# MCU.net
KiCad netlist of a schematic drawn in Altium Designer
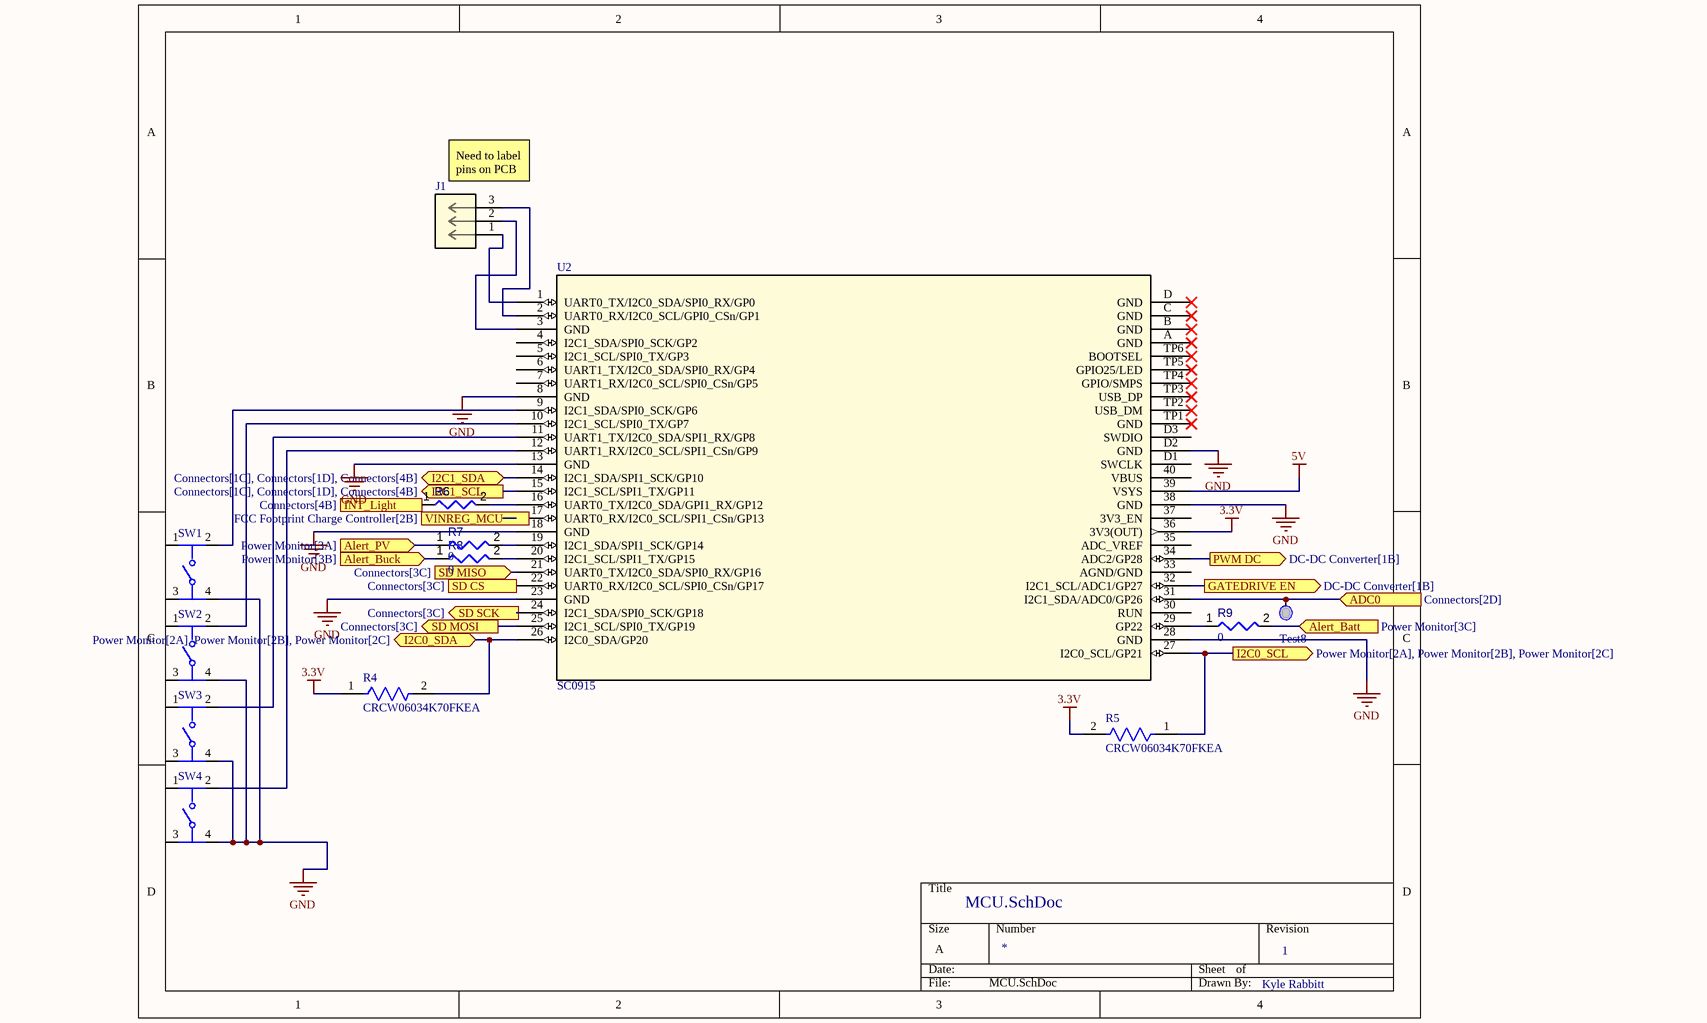
[diagram p0: MCU.SchDoc]

(export (version "E")
  (design (tool "Eeschema 10.0.6"))
  (components
    (comp (ref "J1")
      (value "~")
      (footprint "CONN_BM03B-SRSS-TBLFSN_JST")
      (description "No Description Available")
      (libsource (lib "BM03B-SRSS-TBLFSN") (part "BM03B-SRSS-TBLFSN"))
    )
    (comp (ref "R4")
      (value "CRCW06034K70FKEA")
      (footprint "FP-CRCW0603-e3-IPC_A")
      (description "RES Thick Film, 4.7kΩ, 1%, 0.1W, 100ppm/°C, 0603")
      (fields (field (name "TOLERANCE") "1%"))
      (libsource (lib "Altium Content Vault") (part "1029c3af85768c4190bb7ad29bc67b5"))
    )
    (comp (ref "R5")
      (value "CRCW06034K70FKEA")
      (footprint "FP-CRCW0603-e3-IPC_A")
      (description "RES Thick Film, 4.7kΩ, 1%, 0.1W, 100ppm/°C, 0603")
      (fields (field (name "TOLERANCE") "1%"))
      (libsource (lib "Altium Content Vault") (part "1029c3af85768c4190bb7ad29bc67b5"))
    )
    (comp (ref "R6")
      (value "0")
      (footprint "RESC0603(1608)_L")
      (description "Jumper 0603 (1608 Metric)")
      (fields (field (name "Comment") "0R3J"))
      (libsource (lib "WPI High Power Rocketry Club") (part "0R3J"))
    )
    (comp (ref "R7")
      (value "0")
      (footprint "RESC0603(1608)_L")
      (description "Jumper 0603 (1608 Metric)")
      (fields (field (name "Comment") "0R3J"))
      (libsource (lib "WPI High Power Rocketry Club") (part "0R3J"))
    )
    (comp (ref "R8")
      (value "0")
      (footprint "RESC0603(1608)_L")
      (description "Jumper 0603 (1608 Metric)")
      (fields (field (name "Comment") "0R3J"))
      (libsource (lib "WPI High Power Rocketry Club") (part "0R3J"))
    )
    (comp (ref "R9")
      (value "0")
      (footprint "RESC0603(1608)_L")
      (description "Jumper 0603 (1608 Metric)")
      (fields (field (name "Comment") "0R3J"))
      (libsource (lib "WPI High Power Rocketry Club") (part "0R3J"))
    )
    (comp (ref "SW1")
      (value "~")
      (footprint "FP-PTS645SM43SMTR92LFS-MFG")
      (description "SWITCH TACTILE SPST-NO 0.05A 12V")
      (libsource (lib "Altium Content Vault") (part "1adf0dd01260c80cf25a44bfd6b99ba"))
    )
    (comp (ref "SW2")
      (value "~")
      (footprint "FP-PTS645SM43SMTR92LFS-MFG")
      (description "SWITCH TACTILE SPST-NO 0.05A 12V")
      (libsource (lib "Altium Content Vault") (part "1adf0dd01260c80cf25a44bfd6b99ba"))
    )
    (comp (ref "SW3")
      (value "~")
      (footprint "FP-PTS645SM43SMTR92LFS-MFG")
      (description "SWITCH TACTILE SPST-NO 0.05A 12V")
      (libsource (lib "Altium Content Vault") (part "1adf0dd01260c80cf25a44bfd6b99ba"))
    )
    (comp (ref "SW4")
      (value "~")
      (footprint "FP-PTS645SM43SMTR92LFS-MFG")
      (description "SWITCH TACTILE SPST-NO 0.05A 12V")
      (libsource (lib "Altium Content Vault") (part "1adf0dd01260c80cf25a44bfd6b99ba"))
    )
    (comp (ref "Test8")
      (value "TestPoint")
      (footprint "Test_IN")
      (libsource (lib "Test_POINTS") (part "TestPoint"))
    )
    (comp (ref "U2")
      (value "SC0915")
      (footprint "SC0915_RPI")
      (description "No Description Available")
      (libsource (lib "SC0915") (part "SC0915"))
    )
  )
  (nets
    (net (code "1") (name "/ADC0") (class "Default")
      (node (ref "Test8") (pin "IN") (pinfunction "IN_IN") (pintype "input"))
      (node (ref "U2") (pin "31") (pinfunction "I2C1_SDA/ADC0/GP26_31") (pintype "bidirectional"))
    )
    (net (code "2") (name "/Alert_Batt") (class "Default")
      (node (ref "R9") (pin "2") (pinfunction "2_2") (pintype "passive"))
    )
    (net (code "3") (name "/Alert_Buck") (class "Default")
      (node (ref "R8") (pin "1") (pinfunction "1_1") (pintype "passive"))
    )
    (net (code "4") (name "/Alert_PV") (class "Default")
      (node (ref "R7") (pin "1") (pinfunction "1_1") (pintype "passive"))
    )
    (net (code "5") (name "/GATEDRIVE EN") (class "Default")
      (node (ref "U2") (pin "32") (pinfunction "I2C1_SCL/ADC1/GP27_32") (pintype "bidirectional"))
    )
    (net (code "6") (name "/I2C0_SCL") (class "Default")
      (node (ref "R5") (pin "1") (pinfunction "1_1") (pintype "passive"))
      (node (ref "U2") (pin "27") (pinfunction "I2C0_SCL/GP21_27") (pintype "bidirectional"))
    )
    (net (code "7") (name "/I2C0_SDA") (class "Default")
      (node (ref "R4") (pin "2") (pinfunction "2_2") (pintype "passive"))
      (node (ref "U2") (pin "26") (pinfunction "I2C0_SDA/GP20_26") (pintype "bidirectional"))
    )
    (net (code "8") (name "/I2C1_SCL") (class "Default")
      (node (ref "U2") (pin "15") (pinfunction "I2C1_SCL/SPI1_TX/GP11_15") (pintype "bidirectional"))
    )
    (net (code "9") (name "/I2C1_SDA") (class "Default")
      (node (ref "U2") (pin "14") (pinfunction "I2C1_SDA/SPI1_SCK/GP10_14") (pintype "bidirectional"))
    )
    (net (code "10") (name "/INT_Light") (class "Default")
      (node (ref "R6") (pin "1") (pinfunction "1_1") (pintype "passive"))
    )
    (net (code "11") (name "/PWM DC") (class "Default")
      (node (ref "U2") (pin "34") (pinfunction "ADC2/GP28_34") (pintype "bidirectional"))
    )
    (net (code "12") (name "/SD CS") (class "Default")
      (node (ref "U2") (pin "22") (pinfunction "UART0_RX/I2C0_SCL/SPI0_CSn/GP17_22") (pintype "bidirectional"))
    )
    (net (code "13") (name "/SD MISO") (class "Default")
      (node (ref "U2") (pin "21") (pinfunction "UART0_TX/I2C0_SDA/SPI0_RX/GP16_21") (pintype "bidirectional"))
    )
    (net (code "14") (name "/SD MOSI") (class "Default")
      (node (ref "U2") (pin "25") (pinfunction "I2C1_SCL/SPI0_TX/GP19_25") (pintype "bidirectional"))
    )
    (net (code "15") (name "/SD SCK") (class "Default")
      (node (ref "U2") (pin "24") (pinfunction "I2C1_SDA/SPI0_SCK/GP18_24") (pintype "bidirectional"))
    )
    (net (code "17") (name "3.3V") (class "Default")
      (node (ref "R4") (pin "1") (pinfunction "1_1") (pintype "passive"))
      (node (ref "R5") (pin "2") (pinfunction "2_2") (pintype "passive"))
      (node (ref "U2") (pin "36") (pinfunction "3V3(OUT)_36") (pintype "output"))
    )
    (net (code "18") (name "5V") (class "Default")
      (node (ref "U2") (pin "39") (pinfunction "VSYS_39") (pintype "power_in"))
    )
    (net (code "19") (name "GND") (class "Default")
      (node (ref "SW1") (pin "4") (pinfunction "4_4") (pintype "passive"))
      (node (ref "SW2") (pin "4") (pinfunction "4_4") (pintype "passive"))
      (node (ref "SW3") (pin "4") (pinfunction "4_4") (pintype "passive"))
      (node (ref "SW4") (pin "4") (pinfunction "4_4") (pintype "passive"))
      (node (ref "U2") (pin "13") (pinfunction "GND_13") (pintype "power_in"))
      (node (ref "U2") (pin "18") (pinfunction "GND_18") (pintype "power_in"))
      (node (ref "U2") (pin "23") (pinfunction "GND_23") (pintype "power_in"))
      (node (ref "U2") (pin "28") (pinfunction "GND_28") (pintype "power_in"))
      (node (ref "U2") (pin "38") (pinfunction "GND_38") (pintype "power_in"))
      (node (ref "U2") (pin "8") (pinfunction "GND_8") (pintype "power_in"))
      (node (ref "U2") (pin "D2") (pinfunction "GND_D2") (pintype "power_in"))
    )
    (net (code "20") (name "Net-(J1-Pad2)") (class "Default")
      (node (ref "J1") (pin "2") (pinfunction "2_2") (pintype "passive"))
      (node (ref "U2") (pin "3") (pinfunction "GND_3") (pintype "power_in"))
    )
    (net (code "21") (name "Net-(U2-GP22)") (class "Default")
      (node (ref "R9") (pin "1") (pinfunction "1_1") (pintype "passive"))
      (node (ref "U2") (pin "29") (pinfunction "GP22_29") (pintype "bidirectional"))
    )
    (net (code "22") (name "Net-(U2-I2C1_SCL{slash}SPI0_TX{slash}GP7)") (class "Default")
      (node (ref "SW2") (pin "2") (pinfunction "2_2") (pintype "passive"))
      (node (ref "U2") (pin "10") (pinfunction "I2C1_SCL/SPI0_TX/GP7_10") (pintype "bidirectional"))
    )
    (net (code "23") (name "Net-(U2-I2C1_SCL{slash}SPI1_TX{slash}GP15)") (class "Default")
      (node (ref "R8") (pin "2") (pinfunction "2_2") (pintype "passive"))
      (node (ref "U2") (pin "20") (pinfunction "I2C1_SCL/SPI1_TX/GP15_20") (pintype "bidirectional"))
    )
    (net (code "24") (name "Net-(U2-I2C1_SDA{slash}SPI0_SCK{slash}GP6)") (class "Default")
      (node (ref "SW1") (pin "2") (pinfunction "2_2") (pintype "passive"))
      (node (ref "U2") (pin "9") (pinfunction "I2C1_SDA/SPI0_SCK/GP6_9") (pintype "bidirectional"))
    )
    (net (code "25") (name "Net-(U2-I2C1_SDA{slash}SPI1_SCK{slash}GP14)") (class "Default")
      (node (ref "R7") (pin "2") (pinfunction "2_2") (pintype "passive"))
      (node (ref "U2") (pin "19") (pinfunction "I2C1_SDA/SPI1_SCK/GP14_19") (pintype "bidirectional"))
    )
    (net (code "26") (name "Net-(U2-UART0_RX{slash}I2C0_SCL{slash}GPI0_CSn{slash}GP1)") (class "Default")
      (node (ref "J1") (pin "3") (pinfunction "3_3") (pintype "passive"))
      (node (ref "U2") (pin "2") (pinfunction "UART0_RX/I2C0_SCL/GPI0_CSn/GP1_2") (pintype "bidirectional"))
    )
    (net (code "27") (name "Net-(U2-UART0_TX{slash}I2C0_SDA{slash}GPI1_RX{slash}GP12)") (class "Default")
      (node (ref "R6") (pin "2") (pinfunction "2_2") (pintype "passive"))
      (node (ref "U2") (pin "16") (pinfunction "UART0_TX/I2C0_SDA/GPI1_RX/GP12_16") (pintype "bidirectional"))
    )
    (net (code "28") (name "Net-(U2-UART0_TX{slash}I2C0_SDA{slash}SPI0_RX{slash}GP0)") (class "Default")
      (node (ref "J1") (pin "1") (pinfunction "1_1") (pintype "passive"))
      (node (ref "U2") (pin "1") (pinfunction "UART0_TX/I2C0_SDA/SPI0_RX/GP0_1") (pintype "bidirectional"))
    )
    (net (code "29") (name "Net-(U2-UART1_RX{slash}I2C0_SCL{slash}SPI1_CSn{slash}GP9)") (class "Default")
      (node (ref "SW4") (pin "2") (pinfunction "2_2") (pintype "passive"))
      (node (ref "U2") (pin "12") (pinfunction "UART1_RX/I2C0_SCL/SPI1_CSn/GP9_12") (pintype "bidirectional"))
    )
    (net (code "30") (name "Net-(U2-UART1_TX{slash}I2C0_SDA{slash}SPI1_RX{slash}GP8)") (class "Default")
      (node (ref "SW3") (pin "2") (pinfunction "2_2") (pintype "passive"))
      (node (ref "U2") (pin "11") (pinfunction "UART1_TX/I2C0_SDA/SPI1_RX/GP8_11") (pintype "bidirectional"))
    )
    (net (code "31") (name "unconnected-(SW1-Pad1)") (class "Default")
      (node (ref "SW1") (pin "1") (pinfunction "1_1") (pintype "passive"))
    )
    (net (code "32") (name "unconnected-(SW1-Pad3)") (class "Default")
      (node (ref "SW1") (pin "3") (pinfunction "3_3") (pintype "passive"))
    )
    (net (code "33") (name "unconnected-(SW2-Pad1)") (class "Default")
      (node (ref "SW2") (pin "1") (pinfunction "1_1") (pintype "passive"))
    )
    (net (code "34") (name "unconnected-(SW2-Pad3)") (class "Default")
      (node (ref "SW2") (pin "3") (pinfunction "3_3") (pintype "passive"))
    )
    (net (code "35") (name "unconnected-(SW3-Pad1)") (class "Default")
      (node (ref "SW3") (pin "1") (pinfunction "1_1") (pintype "passive"))
    )
    (net (code "36") (name "unconnected-(SW3-Pad3)") (class "Default")
      (node (ref "SW3") (pin "3") (pinfunction "3_3") (pintype "passive"))
    )
    (net (code "37") (name "unconnected-(SW4-Pad1)") (class "Default")
      (node (ref "SW4") (pin "1") (pinfunction "1_1") (pintype "passive"))
    )
    (net (code "38") (name "unconnected-(SW4-Pad3)") (class "Default")
      (node (ref "SW4") (pin "3") (pinfunction "3_3") (pintype "passive"))
    )
    (net (code "39") (name "unconnected-(U2-3V3_EN-Pad37)") (class "Default")
      (node (ref "U2") (pin "37") (pinfunction "3V3_EN_37") (pintype "power_in"))
    )
    (net (code "40") (name "unconnected-(U2-ADC_VREF-Pad35)") (class "Default")
      (node (ref "U2") (pin "35") (pinfunction "ADC_VREF_35") (pintype "power_in"))
    )
    (net (code "41") (name "unconnected-(U2-AGND{slash}GND-Pad33)") (class "Default")
      (node (ref "U2") (pin "33") (pinfunction "AGND/GND_33") (pintype "power_in"))
    )
    (net (code "42") (name "unconnected-(U2-BOOTSEL-PadTP6)") (class "Default")
      (node (ref "U2") (pin "TP6") (pinfunction "BOOTSEL_TP6") (pintype "passive+no_connect"))
    )
    (net (code "43") (name "unconnected-(U2-GND-PadA)") (class "Default")
      (node (ref "U2") (pin "A") (pinfunction "GND_A") (pintype "power_in+no_connect"))
    )
    (net (code "44") (name "unconnected-(U2-GND-PadB)") (class "Default")
      (node (ref "U2") (pin "B") (pinfunction "GND_B") (pintype "power_in+no_connect"))
    )
    (net (code "45") (name "unconnected-(U2-GND-PadC)") (class "Default")
      (node (ref "U2") (pin "C") (pinfunction "GND_C") (pintype "power_in+no_connect"))
    )
    (net (code "46") (name "unconnected-(U2-GND-PadD)") (class "Default")
      (node (ref "U2") (pin "D") (pinfunction "GND_D") (pintype "power_in+no_connect"))
    )
    (net (code "47") (name "unconnected-(U2-GND-PadTP1)") (class "Default")
      (node (ref "U2") (pin "TP1") (pinfunction "GND_TP1") (pintype "power_in+no_connect"))
    )
    (net (code "48") (name "unconnected-(U2-GPIO25{slash}LED-PadTP5)") (class "Default")
      (node (ref "U2") (pin "TP5") (pinfunction "GPIO25/LED_TP5") (pintype "passive+no_connect"))
    )
    (net (code "49") (name "unconnected-(U2-GPIO{slash}SMPS-PadTP4)") (class "Default")
      (node (ref "U2") (pin "TP4") (pinfunction "GPIO/SMPS_TP4") (pintype "passive+no_connect"))
    )
    (net (code "50") (name "unconnected-(U2-I2C1_SCL{slash}SPI0_TX{slash}GP3-Pad5)") (class "Default")
      (node (ref "U2") (pin "5") (pinfunction "I2C1_SCL/SPI0_TX/GP3_5") (pintype "bidirectional"))
    )
    (net (code "51") (name "unconnected-(U2-I2C1_SDA{slash}SPI0_SCK{slash}GP2-Pad4)") (class "Default")
      (node (ref "U2") (pin "4") (pinfunction "I2C1_SDA/SPI0_SCK/GP2_4") (pintype "bidirectional"))
    )
    (net (code "52") (name "unconnected-(U2-RUN-Pad30)") (class "Default")
      (node (ref "U2") (pin "30") (pinfunction "RUN_30") (pintype "passive"))
    )
    (net (code "53") (name "unconnected-(U2-SWCLK-PadD1)") (class "Default")
      (node (ref "U2") (pin "D1") (pinfunction "SWCLK_D1") (pintype "passive"))
    )
    (net (code "54") (name "unconnected-(U2-SWDIO-PadD3)") (class "Default")
      (node (ref "U2") (pin "D3") (pinfunction "SWDIO_D3") (pintype "passive"))
    )
    (net (code "55") (name "unconnected-(U2-UART0_RX{slash}I2C0_SCL{slash}SPI1_CSn{slash}GP13-Pad17)") (class "Default")
      (node (ref "U2") (pin "17") (pinfunction "UART0_RX/I2C0_SCL/SPI1_CSn/GP13_17") (pintype "bidirectional"))
    )
    (net (code "56") (name "unconnected-(U2-UART1_RX{slash}I2C0_SCL{slash}SPI0_CSn{slash}GP5-Pad7)") (class "Default")
      (node (ref "U2") (pin "7") (pinfunction "UART1_RX/I2C0_SCL/SPI0_CSn/GP5_7") (pintype "bidirectional"))
    )
    (net (code "57") (name "unconnected-(U2-UART1_TX{slash}I2C0_SDA{slash}SPI0_RX{slash}GP4-Pad6)") (class "Default")
      (node (ref "U2") (pin "6") (pinfunction "UART1_TX/I2C0_SDA/SPI0_RX/GP4_6") (pintype "bidirectional"))
    )
    (net (code "58") (name "unconnected-(U2-USB_DM-PadTP2)") (class "Default")
      (node (ref "U2") (pin "TP2") (pinfunction "USB_DM_TP2") (pintype "passive+no_connect"))
    )
    (net (code "59") (name "unconnected-(U2-USB_DP-PadTP3)") (class "Default")
      (node (ref "U2") (pin "TP3") (pinfunction "USB_DP_TP3") (pintype "passive+no_connect"))
    )
    (net (code "60") (name "unconnected-(U2-VBUS-Pad40)") (class "Default")
      (node (ref "U2") (pin "40") (pinfunction "VBUS_40") (pintype "power_in"))
    )
  )
)
